# Super-Regenerative-FM-Tuner.net
KiCad netlist of a schematic drawn in EAGLE
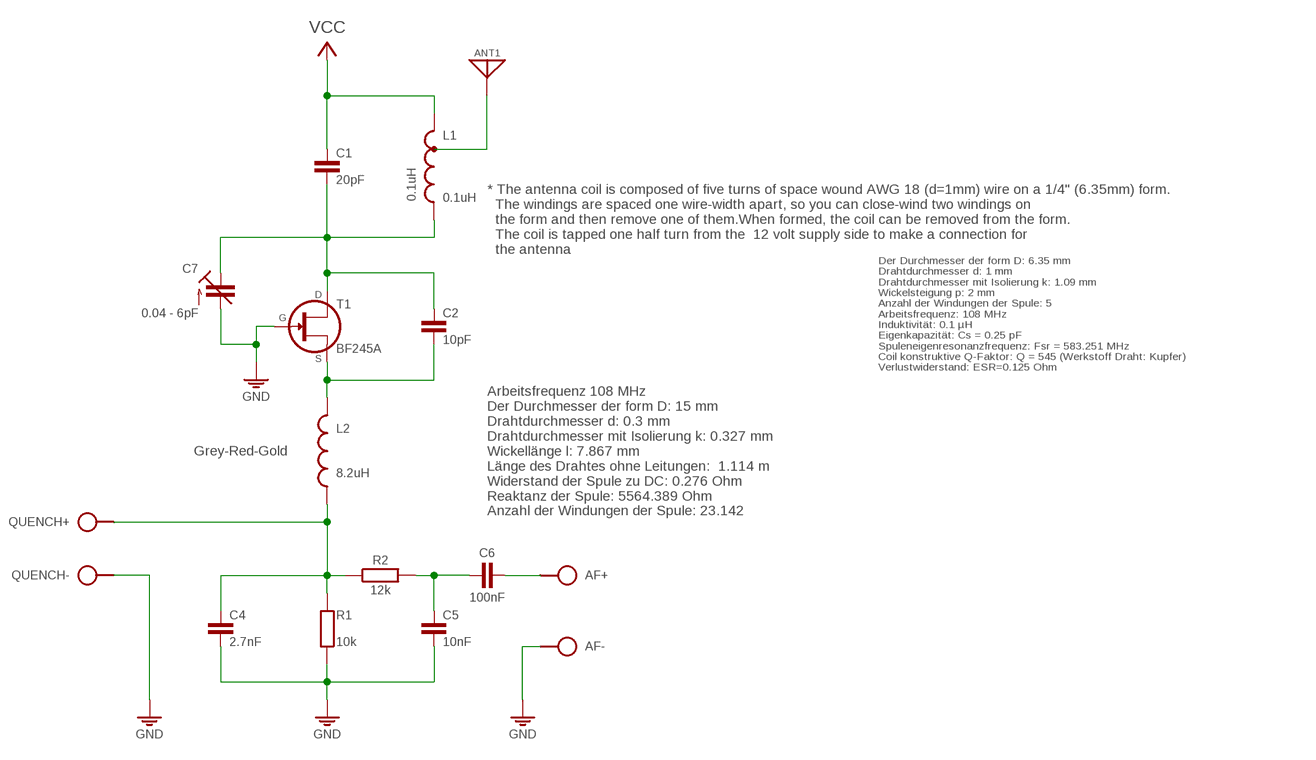
[diagram p0: schematic, sheet 1]

(export (version "E")
  (design (tool "Eeschema 10.0.6"))
  (components
    (comp (ref "AF")
      (value "SPAD+-+-")
      (footprint "eagle-import:SPAD+-")
      (libsource (lib "eagle-import") (part "SPAD+-+-"))
    )
    (comp (ref "ANT1")
      (value "ANT")
      (footprint "eagle-import:SPAD")
      (libsource (lib "eagle-import") (part "ANT"))
    )
    (comp (ref "C1")
      (value "20pF")
      (footprint "eagle-import:C025-015X024")
      (libsource (lib "eagle-import") (part "C025-015X024"))
    )
    (comp (ref "C2")
      (value "10pF")
      (footprint "eagle-import:C025-015X024")
      (libsource (lib "eagle-import") (part "C025-015X024"))
    )
    (comp (ref "C4")
      (value "2.7nF")
      (footprint "eagle-import:C050-020X044")
      (libsource (lib "eagle-import") (part "C050-020X044"))
    )
    (comp (ref "C5")
      (value "10nF")
      (footprint "eagle-import:C050-020X044")
      (libsource (lib "eagle-import") (part "C050-020X044"))
    )
    (comp (ref "C6")
      (value "100nF")
      (footprint "eagle-import:C050-020X044")
      (libsource (lib "eagle-import") (part "C-H050-020X044"))
    )
    (comp (ref "C7")
      (value "0.04 - 6pF")
      (footprint "eagle-import:CTRIMTZ03")
      (libsource (lib "eagle-import") (part "C-TR-PH20127-TZ03"))
    )
    (comp (ref "L1")
      (value "0.1uH")
      (footprint "eagle-import:L-08_10V-TAP1")
      (libsource (lib "eagle-import") (part "L-TAP1L-08/10V-TAP1"))
    )
    (comp (ref "L2")
      (value "8.2uH")
      (footprint "eagle-import:L-04_7-V")
      (libsource (lib "eagle-import") (part "L04/7-V"))
    )
    (comp (ref "PWR")
      (value "VCC_GNDL")
      (footprint "eagle-import:SPAD-+")
      (libsource (lib "eagle-import") (part "VCC_GNDL"))
    )
    (comp (ref "QUENCH")
      (value "SPAD+--+")
      (footprint "eagle-import:SPAD-+")
      (libsource (lib "eagle-import") (part "SPAD+--+"))
    )
    (comp (ref "R1")
      (value "10k")
      (footprint "eagle-import:0204_10-V")
      (libsource (lib "eagle-import") (part "R0204/10-V"))
    )
    (comp (ref "R2")
      (value "12k")
      (footprint "eagle-import:0204_10-V")
      (libsource (lib "eagle-import") (part "R-H0204/10-V"))
    )
    (comp (ref "T1")
      (value "BF245A")
      (footprint "eagle-import:TO92-GSD")
      (libsource (lib "eagle-import") (part "BF245BTO92"))
    )
  )
  (nets
    (net (code "1") (name "GND") (class "Default")
      (node (ref "AF") (pin "1") (pinfunction "P$1_1") (pintype "passive"))
      (node (ref "C4") (pin "2") (pinfunction "2_2") (pintype "passive"))
      (node (ref "C5") (pin "2") (pinfunction "2_2") (pintype "passive"))
      (node (ref "C7") (pin "1") (pinfunction "A_1") (pintype "passive"))
      (node (ref "PWR") (pin "1") (pinfunction "GND_1") (pintype "power_in"))
      (node (ref "QUENCH") (pin "1") (pinfunction "P$1_1") (pintype "passive"))
      (node (ref "R1") (pin "2") (pinfunction "2_2") (pintype "passive"))
      (node (ref "T1") (pin "1") (pinfunction "G_1") (pintype "passive"))
    )
    (net (code "2") (name "Net-(AFA-P$1)") (class "Default")
      (node (ref "AF") (pin "2") (pinfunction "P$1_2") (pintype "passive"))
      (node (ref "C6") (pin "2") (pinfunction "2_2") (pintype "passive"))
    )
    (net (code "3") (name "Net-(C5-Pad1)") (class "Default")
      (node (ref "C5") (pin "1") (pinfunction "1_1") (pintype "passive"))
      (node (ref "C6") (pin "1") (pinfunction "1_1") (pintype "passive"))
      (node (ref "R2") (pin "2") (pinfunction "2_2") (pintype "passive"))
    )
    (net (code "4") (name "Net-(C7-E)") (class "Default")
      (node (ref "C1") (pin "2") (pinfunction "2_2") (pintype "passive"))
      (node (ref "C2") (pin "1") (pinfunction "1_1") (pintype "passive"))
      (node (ref "C7") (pin "2") (pinfunction "E_2") (pintype "passive"))
      (node (ref "L1") (pin "2") (pinfunction "2_2") (pintype "passive"))
      (node (ref "T1") (pin "3") (pinfunction "D_3") (pintype "passive"))
    )
    (net (code "5") (name "Net-(L1-T)") (class "Default")
      (node (ref "ANT1") (pin "1") (pinfunction "1_1") (pintype "output"))
      (node (ref "L1") (pin "3") (pinfunction "T_3") (pintype "passive"))
    )
    (net (code "6") (name "Net-(PWRB-VCC)") (class "Default")
      (node (ref "C1") (pin "1") (pinfunction "1_1") (pintype "passive"))
      (node (ref "L1") (pin "1") (pinfunction "1_1") (pintype "passive"))
      (node (ref "PWR") (pin "2") (pinfunction "VCC_2") (pintype "power_in"))
    )
    (net (code "7") (name "Net-(QUENCHA-P$1)") (class "Default")
      (node (ref "C4") (pin "1") (pinfunction "1_1") (pintype "passive"))
      (node (ref "L2") (pin "2") (pinfunction "2_2") (pintype "passive"))
      (node (ref "QUENCH") (pin "2") (pinfunction "P$1_2") (pintype "passive"))
      (node (ref "R1") (pin "1") (pinfunction "1_1") (pintype "passive"))
      (node (ref "R2") (pin "1") (pinfunction "1_1") (pintype "passive"))
    )
    (net (code "8") (name "Net-(T1-S)") (class "Default")
      (node (ref "C2") (pin "2") (pinfunction "2_2") (pintype "passive"))
      (node (ref "L2") (pin "1") (pinfunction "1_1") (pintype "passive"))
      (node (ref "T1") (pin "2") (pinfunction "S_2") (pintype "passive"))
    )
  )
)
